# led_matrix.net
KiCad netlist of a schematic drawn in Altium Designer
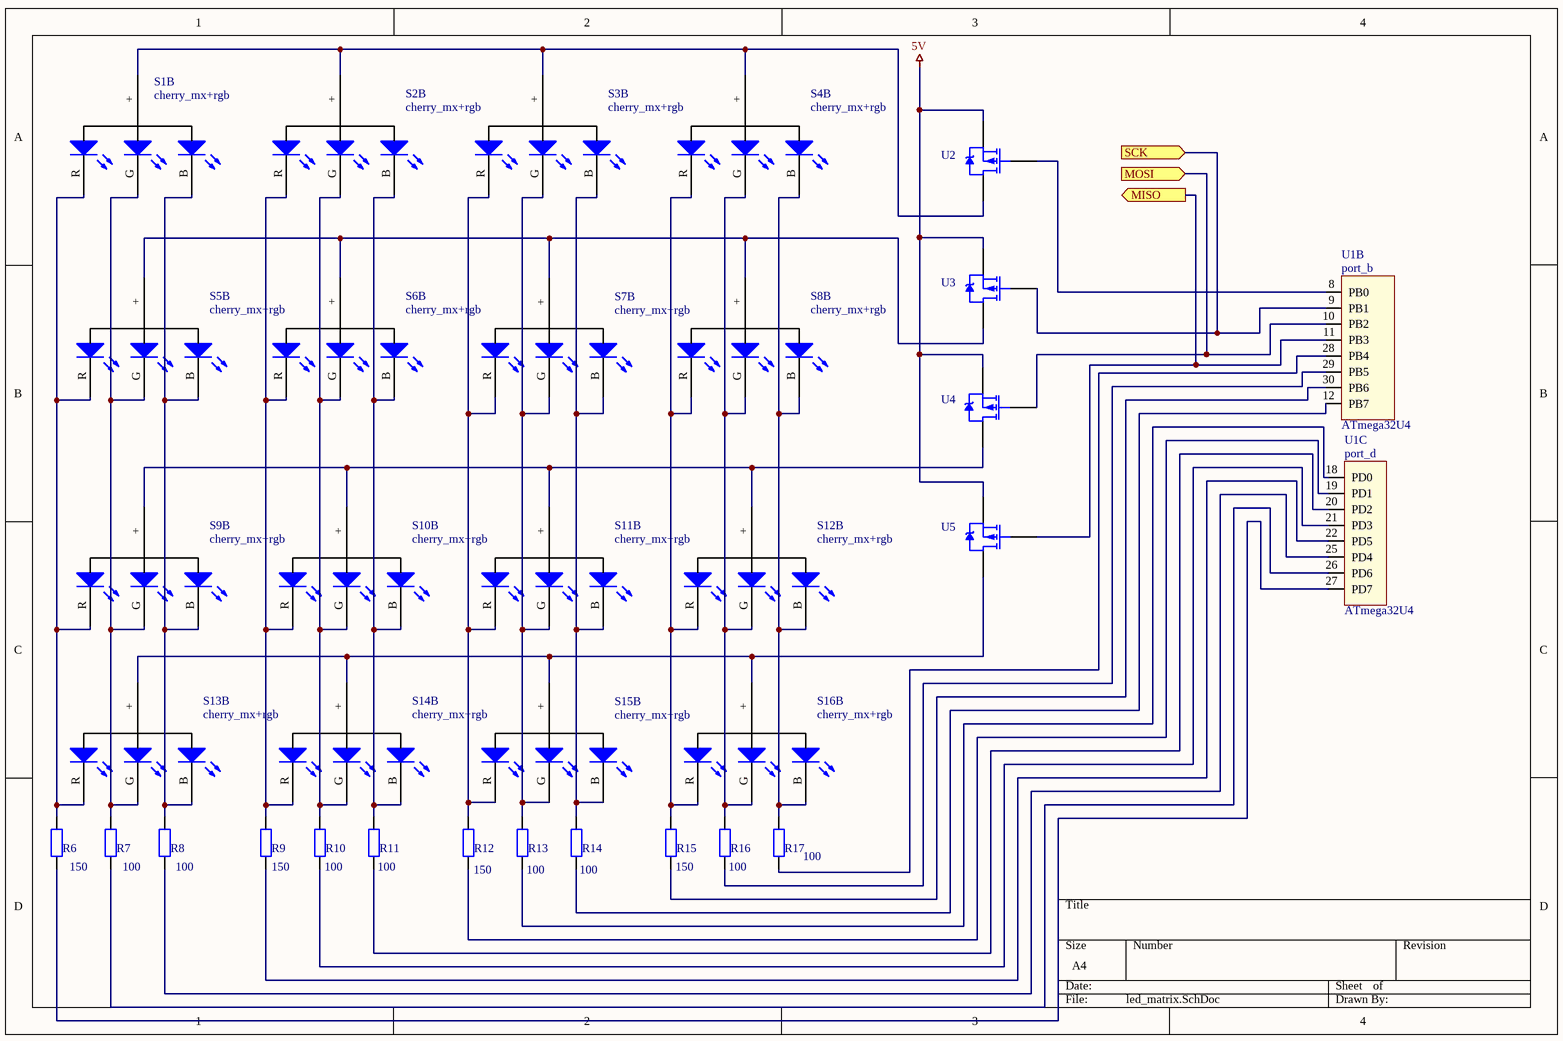
[diagram p0: led_matrix.SchDoc]

(export (version "E")
  (design (tool "Eeschema 10.0.6"))
  (components
    (comp (ref "R6") (value "150") (footprint "0805") (libsource (lib "generic_components") (part "res0805")))
    (comp (ref "R7") (value "100") (footprint "0805") (libsource (lib "generic_components") (part "res0805")))
    (comp (ref "R8") (value "100") (footprint "0805") (libsource (lib "generic_components") (part "res0805")))
    (comp (ref "R9") (value "150") (footprint "0805") (libsource (lib "generic_components") (part "res0805")))
    (comp (ref "R10")
      (value "100")
      (footprint "0805")
      (libsource (lib "generic_components") (part "res0805"))
    )
    (comp (ref "R11")
      (value "100")
      (footprint "0805")
      (libsource (lib "generic_components") (part "res0805"))
    )
    (comp (ref "R12")
      (value "150")
      (footprint "0805")
      (libsource (lib "generic_components") (part "res0805"))
    )
    (comp (ref "R13")
      (value "100")
      (footprint "0805")
      (libsource (lib "generic_components") (part "res0805"))
    )
    (comp (ref "R14")
      (value "100")
      (footprint "0805")
      (libsource (lib "generic_components") (part "res0805"))
    )
    (comp (ref "R15")
      (value "150")
      (footprint "0805")
      (libsource (lib "generic_components") (part "res0805"))
    )
    (comp (ref "R16")
      (value "100")
      (footprint "0805")
      (libsource (lib "generic_components") (part "res0805"))
    )
    (comp (ref "R17")
      (value "100")
      (footprint "0805")
      (libsource (lib "generic_components") (part "res0805"))
    )
    (comp (ref "S1")
      (value "cherry_mx+rgb")
      (footprint "kailh_socket_mx+led")
      (libsource (lib "mx") (part "cherry_mx+rgb"))
    )
    (comp (ref "S2")
      (value "cherry_mx+rgb")
      (footprint "kailh_socket_mx+led")
      (libsource (lib "mx") (part "cherry_mx+rgb"))
    )
    (comp (ref "S3")
      (value "cherry_mx+rgb")
      (footprint "kailh_socket_mx+led")
      (libsource (lib "mx") (part "cherry_mx+rgb"))
    )
    (comp (ref "S4")
      (value "cherry_mx+rgb")
      (footprint "kailh_socket_mx+led")
      (libsource (lib "mx") (part "cherry_mx+rgb"))
    )
    (comp (ref "S5")
      (value "cherry_mx+rgb")
      (footprint "kailh_socket_mx+led")
      (libsource (lib "mx") (part "cherry_mx+rgb"))
    )
    (comp (ref "S6")
      (value "cherry_mx+rgb")
      (footprint "kailh_socket_mx+led")
      (libsource (lib "mx") (part "cherry_mx+rgb"))
    )
    (comp (ref "S7")
      (value "cherry_mx+rgb")
      (footprint "kailh_socket_mx+led")
      (libsource (lib "mx") (part "cherry_mx+rgb"))
    )
    (comp (ref "S8")
      (value "cherry_mx+rgb")
      (footprint "kailh_socket_mx+led")
      (libsource (lib "mx") (part "cherry_mx+rgb"))
    )
    (comp (ref "S9")
      (value "cherry_mx+rgb")
      (footprint "kailh_socket_mx+led")
      (libsource (lib "mx") (part "cherry_mx+rgb"))
    )
    (comp (ref "S10")
      (value "cherry_mx+rgb")
      (footprint "kailh_socket_mx+led")
      (libsource (lib "mx") (part "cherry_mx+rgb"))
    )
    (comp (ref "S11")
      (value "cherry_mx+rgb")
      (footprint "kailh_socket_mx+led")
      (libsource (lib "mx") (part "cherry_mx+rgb"))
    )
    (comp (ref "S12")
      (value "cherry_mx+rgb")
      (footprint "kailh_socket_mx+led")
      (libsource (lib "mx") (part "cherry_mx+rgb"))
    )
    (comp (ref "S13")
      (value "cherry_mx+rgb")
      (footprint "kailh_socket_mx+led")
      (libsource (lib "mx") (part "cherry_mx+rgb"))
    )
    (comp (ref "S14")
      (value "cherry_mx+rgb")
      (footprint "kailh_socket_mx+led")
      (libsource (lib "mx") (part "cherry_mx+rgb"))
    )
    (comp (ref "S15")
      (value "cherry_mx+rgb")
      (footprint "kailh_socket_mx+led")
      (libsource (lib "mx") (part "cherry_mx+rgb"))
    )
    (comp (ref "S16")
      (value "cherry_mx+rgb")
      (footprint "kailh_socket_mx+led")
      (libsource (lib "mx") (part "cherry_mx+rgb"))
    )
    (comp (ref "U1")
      (value "ATmega32U4")
      (footprint "QFN44P05P7X7")
      (libsource (lib "atmel") (part "ATmega32U4"))
    )
    (comp (ref "U2")
      (value "P-mosfet_NX300PBK")
      (footprint "SOT23(TO-236AB)P095S230x290")
      (libsource (lib "generic_components") (part "P-mosfet_NX300PBK"))
    )
    (comp (ref "U3")
      (value "P-mosfet_NX300PBK")
      (footprint "SOT23(TO-236AB)P095S230x290")
      (libsource (lib "generic_components") (part "P-mosfet_NX300PBK"))
    )
    (comp (ref "U4")
      (value "P-mosfet_NX300PBK")
      (footprint "SOT23(TO-236AB)P095S230x290")
      (libsource (lib "generic_components") (part "P-mosfet_NX300PBK"))
    )
    (comp (ref "U5")
      (value "P-mosfet_NX300PBK")
      (footprint "SOT23(TO-236AB)P095S230x290")
      (libsource (lib "generic_components") (part "P-mosfet_NX300PBK"))
    )
  )
  (nets
    (net (code "1") (name "/MISO") (class "Default")
      (node (ref "U1") (pin "11") (pinfunction "PB3_11") (pintype "bidirectional"))
      (node (ref "U5") (pin "1") (pinfunction "G_1") (pintype "passive"))
    )
    (net (code "2") (name "/MOSI") (class "Default")
      (node (ref "U1") (pin "10") (pinfunction "PB2_10") (pintype "bidirectional"))
      (node (ref "U4") (pin "1") (pinfunction "G_1") (pintype "passive"))
    )
    (net (code "3") (name "/SCK") (class "Default")
      (node (ref "U1") (pin "9") (pinfunction "PB1_9") (pintype "bidirectional"))
      (node (ref "U3") (pin "1") (pinfunction "G_1") (pintype "passive"))
    )
    (net (code "4") (name "5V") (class "Default")
      (node (ref "U2") (pin "2") (pinfunction "S_2") (pintype "passive"))
      (node (ref "U3") (pin "2") (pinfunction "S_2") (pintype "passive"))
      (node (ref "U4") (pin "2") (pinfunction "S_2") (pintype "passive"))
      (node (ref "U5") (pin "2") (pinfunction "S_2") (pintype "passive"))
    )
    (net (code "5") (name "Net-(R6-Pad2)") (class "Default")
      (node (ref "R6") (pin "2") (pinfunction "2_2") (pintype "passive"))
      (node (ref "S1") (pin "R") (pintype "power_in"))
      (node (ref "S13") (pin "R") (pintype "power_in"))
      (node (ref "S5") (pin "R") (pintype "power_in"))
      (node (ref "S9") (pin "R") (pintype "power_in"))
    )
    (net (code "6") (name "Net-(R7-Pad2)") (class "Default")
      (node (ref "R7") (pin "2") (pinfunction "2_2") (pintype "passive"))
      (node (ref "S1") (pin "G") (pintype "power_in"))
      (node (ref "S13") (pin "G") (pintype "power_in"))
      (node (ref "S5") (pin "G") (pintype "power_in"))
      (node (ref "S9") (pin "G") (pintype "power_in"))
    )
    (net (code "7") (name "Net-(R8-Pad2)") (class "Default")
      (node (ref "R8") (pin "2") (pinfunction "2_2") (pintype "passive"))
      (node (ref "S1") (pin "B") (pintype "power_in"))
      (node (ref "S13") (pin "B") (pintype "power_in"))
      (node (ref "S5") (pin "B") (pintype "power_in"))
      (node (ref "S9") (pin "B") (pintype "power_in"))
    )
    (net (code "8") (name "Net-(R9-Pad2)") (class "Default")
      (node (ref "R9") (pin "2") (pinfunction "2_2") (pintype "passive"))
      (node (ref "S10") (pin "R") (pintype "power_in"))
      (node (ref "S14") (pin "R") (pintype "power_in"))
      (node (ref "S2") (pin "R") (pintype "power_in"))
      (node (ref "S6") (pin "R") (pintype "power_in"))
    )
    (net (code "9") (name "Net-(R10-Pad2)") (class "Default")
      (node (ref "R10") (pin "2") (pinfunction "2_2") (pintype "passive"))
      (node (ref "S10") (pin "G") (pintype "power_in"))
      (node (ref "S14") (pin "G") (pintype "power_in"))
      (node (ref "S2") (pin "G") (pintype "power_in"))
      (node (ref "S6") (pin "G") (pintype "power_in"))
    )
    (net (code "10") (name "Net-(R11-Pad2)") (class "Default")
      (node (ref "R11") (pin "2") (pinfunction "2_2") (pintype "passive"))
      (node (ref "S10") (pin "B") (pintype "power_in"))
      (node (ref "S14") (pin "B") (pintype "power_in"))
      (node (ref "S2") (pin "B") (pintype "power_in"))
      (node (ref "S6") (pin "B") (pintype "power_in"))
    )
    (net (code "11") (name "Net-(R12-Pad2)") (class "Default")
      (node (ref "R12") (pin "2") (pinfunction "2_2") (pintype "passive"))
      (node (ref "S11") (pin "R") (pintype "power_in"))
      (node (ref "S15") (pin "R") (pintype "power_in"))
      (node (ref "S3") (pin "R") (pintype "power_in"))
      (node (ref "S7") (pin "R") (pintype "power_in"))
    )
    (net (code "12") (name "Net-(R13-Pad2)") (class "Default")
      (node (ref "R13") (pin "2") (pinfunction "2_2") (pintype "passive"))
      (node (ref "S11") (pin "G") (pintype "power_in"))
      (node (ref "S15") (pin "G") (pintype "power_in"))
      (node (ref "S3") (pin "G") (pintype "power_in"))
      (node (ref "S7") (pin "G") (pintype "power_in"))
    )
    (net (code "13") (name "Net-(R14-Pad2)") (class "Default")
      (node (ref "R14") (pin "2") (pinfunction "2_2") (pintype "passive"))
      (node (ref "S11") (pin "B") (pintype "power_in"))
      (node (ref "S15") (pin "B") (pintype "power_in"))
      (node (ref "S3") (pin "B") (pintype "power_in"))
      (node (ref "S7") (pin "B") (pintype "power_in"))
    )
    (net (code "14") (name "Net-(R15-Pad2)") (class "Default")
      (node (ref "R15") (pin "2") (pinfunction "2_2") (pintype "passive"))
      (node (ref "S12") (pin "R") (pintype "power_in"))
      (node (ref "S16") (pin "R") (pintype "power_in"))
      (node (ref "S4") (pin "R") (pintype "power_in"))
      (node (ref "S8") (pin "R") (pintype "power_in"))
    )
    (net (code "15") (name "Net-(R16-Pad2)") (class "Default")
      (node (ref "R16") (pin "2") (pinfunction "2_2") (pintype "passive"))
      (node (ref "S12") (pin "G") (pintype "power_in"))
      (node (ref "S16") (pin "G") (pintype "power_in"))
      (node (ref "S4") (pin "G") (pintype "power_in"))
      (node (ref "S8") (pin "G") (pintype "power_in"))
    )
    (net (code "16") (name "Net-(R17-Pad2)") (class "Default")
      (node (ref "R17") (pin "2") (pinfunction "2_2") (pintype "passive"))
      (node (ref "S12") (pin "B") (pintype "power_in"))
      (node (ref "S16") (pin "B") (pintype "power_in"))
      (node (ref "S4") (pin "B") (pintype "power_in"))
      (node (ref "S8") (pin "B") (pintype "power_in"))
    )
    (net (code "17") (name "Net-(U1B-PB0)") (class "Default")
      (node (ref "U1") (pin "8") (pinfunction "PB0_8") (pintype "bidirectional"))
      (node (ref "U2") (pin "1") (pinfunction "G_1") (pintype "passive"))
    )
    (net (code "18") (name "Net-(U1B-PB4)") (class "Default")
      (node (ref "R17") (pin "1") (pintype "passive"))
      (node (ref "U1") (pin "28") (pinfunction "PB4_28") (pintype "bidirectional"))
    )
    (net (code "19") (name "Net-(U1B-PB5)") (class "Default")
      (node (ref "R16") (pin "1") (pintype "passive"))
      (node (ref "U1") (pin "29") (pinfunction "PB5_29") (pintype "bidirectional"))
    )
    (net (code "20") (name "Net-(U1B-PB6)") (class "Default")
      (node (ref "R15") (pin "1") (pintype "passive"))
      (node (ref "U1") (pin "30") (pinfunction "PB6_30") (pintype "bidirectional"))
    )
    (net (code "21") (name "Net-(U1B-PB7)") (class "Default")
      (node (ref "R14") (pin "1") (pintype "passive"))
      (node (ref "U1") (pin "12") (pinfunction "PB7_12") (pintype "bidirectional"))
    )
    (net (code "22") (name "Net-(U1C-PD0)") (class "Default")
      (node (ref "R13") (pin "1") (pintype "passive"))
      (node (ref "U1") (pin "18") (pinfunction "PD0_18") (pintype "bidirectional"))
    )
    (net (code "23") (name "Net-(U1C-PD1)") (class "Default")
      (node (ref "R12") (pin "1") (pintype "passive"))
      (node (ref "U1") (pin "19") (pinfunction "PD1_19") (pintype "bidirectional"))
    )
    (net (code "24") (name "Net-(U1C-PD2)") (class "Default")
      (node (ref "R11") (pin "1") (pintype "passive"))
      (node (ref "U1") (pin "20") (pinfunction "PD2_20") (pintype "bidirectional"))
    )
    (net (code "25") (name "Net-(U1C-PD3)") (class "Default")
      (node (ref "R10") (pin "1") (pintype "passive"))
      (node (ref "U1") (pin "21") (pinfunction "PD3_21") (pintype "bidirectional"))
    )
    (net (code "26") (name "Net-(U1C-PD4)") (class "Default")
      (node (ref "R8") (pin "1") (pintype "passive"))
      (node (ref "U1") (pin "25") (pinfunction "PD4_25") (pintype "bidirectional"))
    )
    (net (code "27") (name "Net-(U1C-PD5)") (class "Default")
      (node (ref "R9") (pin "1") (pintype "passive"))
      (node (ref "U1") (pin "22") (pinfunction "PD5_22") (pintype "bidirectional"))
    )
    (net (code "28") (name "Net-(U1C-PD6)") (class "Default")
      (node (ref "R7") (pin "1") (pintype "passive"))
      (node (ref "U1") (pin "26") (pinfunction "PD6_26") (pintype "bidirectional"))
    )
    (net (code "29") (name "Net-(U1C-PD7)") (class "Default")
      (node (ref "R6") (pin "1") (pintype "passive"))
      (node (ref "U1") (pin "27") (pinfunction "PD7_27") (pintype "bidirectional"))
    )
    (net (code "30") (name "Net-(U2-D)") (class "Default")
      (node (ref "S1") (pin "+") (pintype "passive"))
      (node (ref "S2") (pin "+") (pintype "passive"))
      (node (ref "S3") (pin "+") (pintype "passive"))
      (node (ref "S4") (pin "+") (pintype "passive"))
      (node (ref "U2") (pin "3") (pinfunction "D_3") (pintype "passive"))
    )
    (net (code "31") (name "Net-(U3-D)") (class "Default")
      (node (ref "S5") (pin "+") (pintype "passive"))
      (node (ref "S6") (pin "+") (pintype "passive"))
      (node (ref "S7") (pin "+") (pintype "passive"))
      (node (ref "S8") (pin "+") (pintype "passive"))
      (node (ref "U3") (pin "3") (pinfunction "D_3") (pintype "passive"))
    )
    (net (code "32") (name "Net-(U4-D)") (class "Default")
      (node (ref "S10") (pin "+") (pintype "passive"))
      (node (ref "S11") (pin "+") (pintype "passive"))
      (node (ref "S12") (pin "+") (pintype "passive"))
      (node (ref "S9") (pin "+") (pintype "passive"))
      (node (ref "U4") (pin "3") (pinfunction "D_3") (pintype "passive"))
    )
    (net (code "33") (name "Net-(U5-D)") (class "Default")
      (node (ref "S13") (pin "+") (pintype "passive"))
      (node (ref "S14") (pin "+") (pintype "passive"))
      (node (ref "S15") (pin "+") (pintype "passive"))
      (node (ref "S16") (pin "+") (pintype "passive"))
      (node (ref "U5") (pin "3") (pinfunction "D_3") (pintype "passive"))
    )
  )
)
